# VCO_channel.net
KiCad netlist of a schematic drawn in Altium Designer
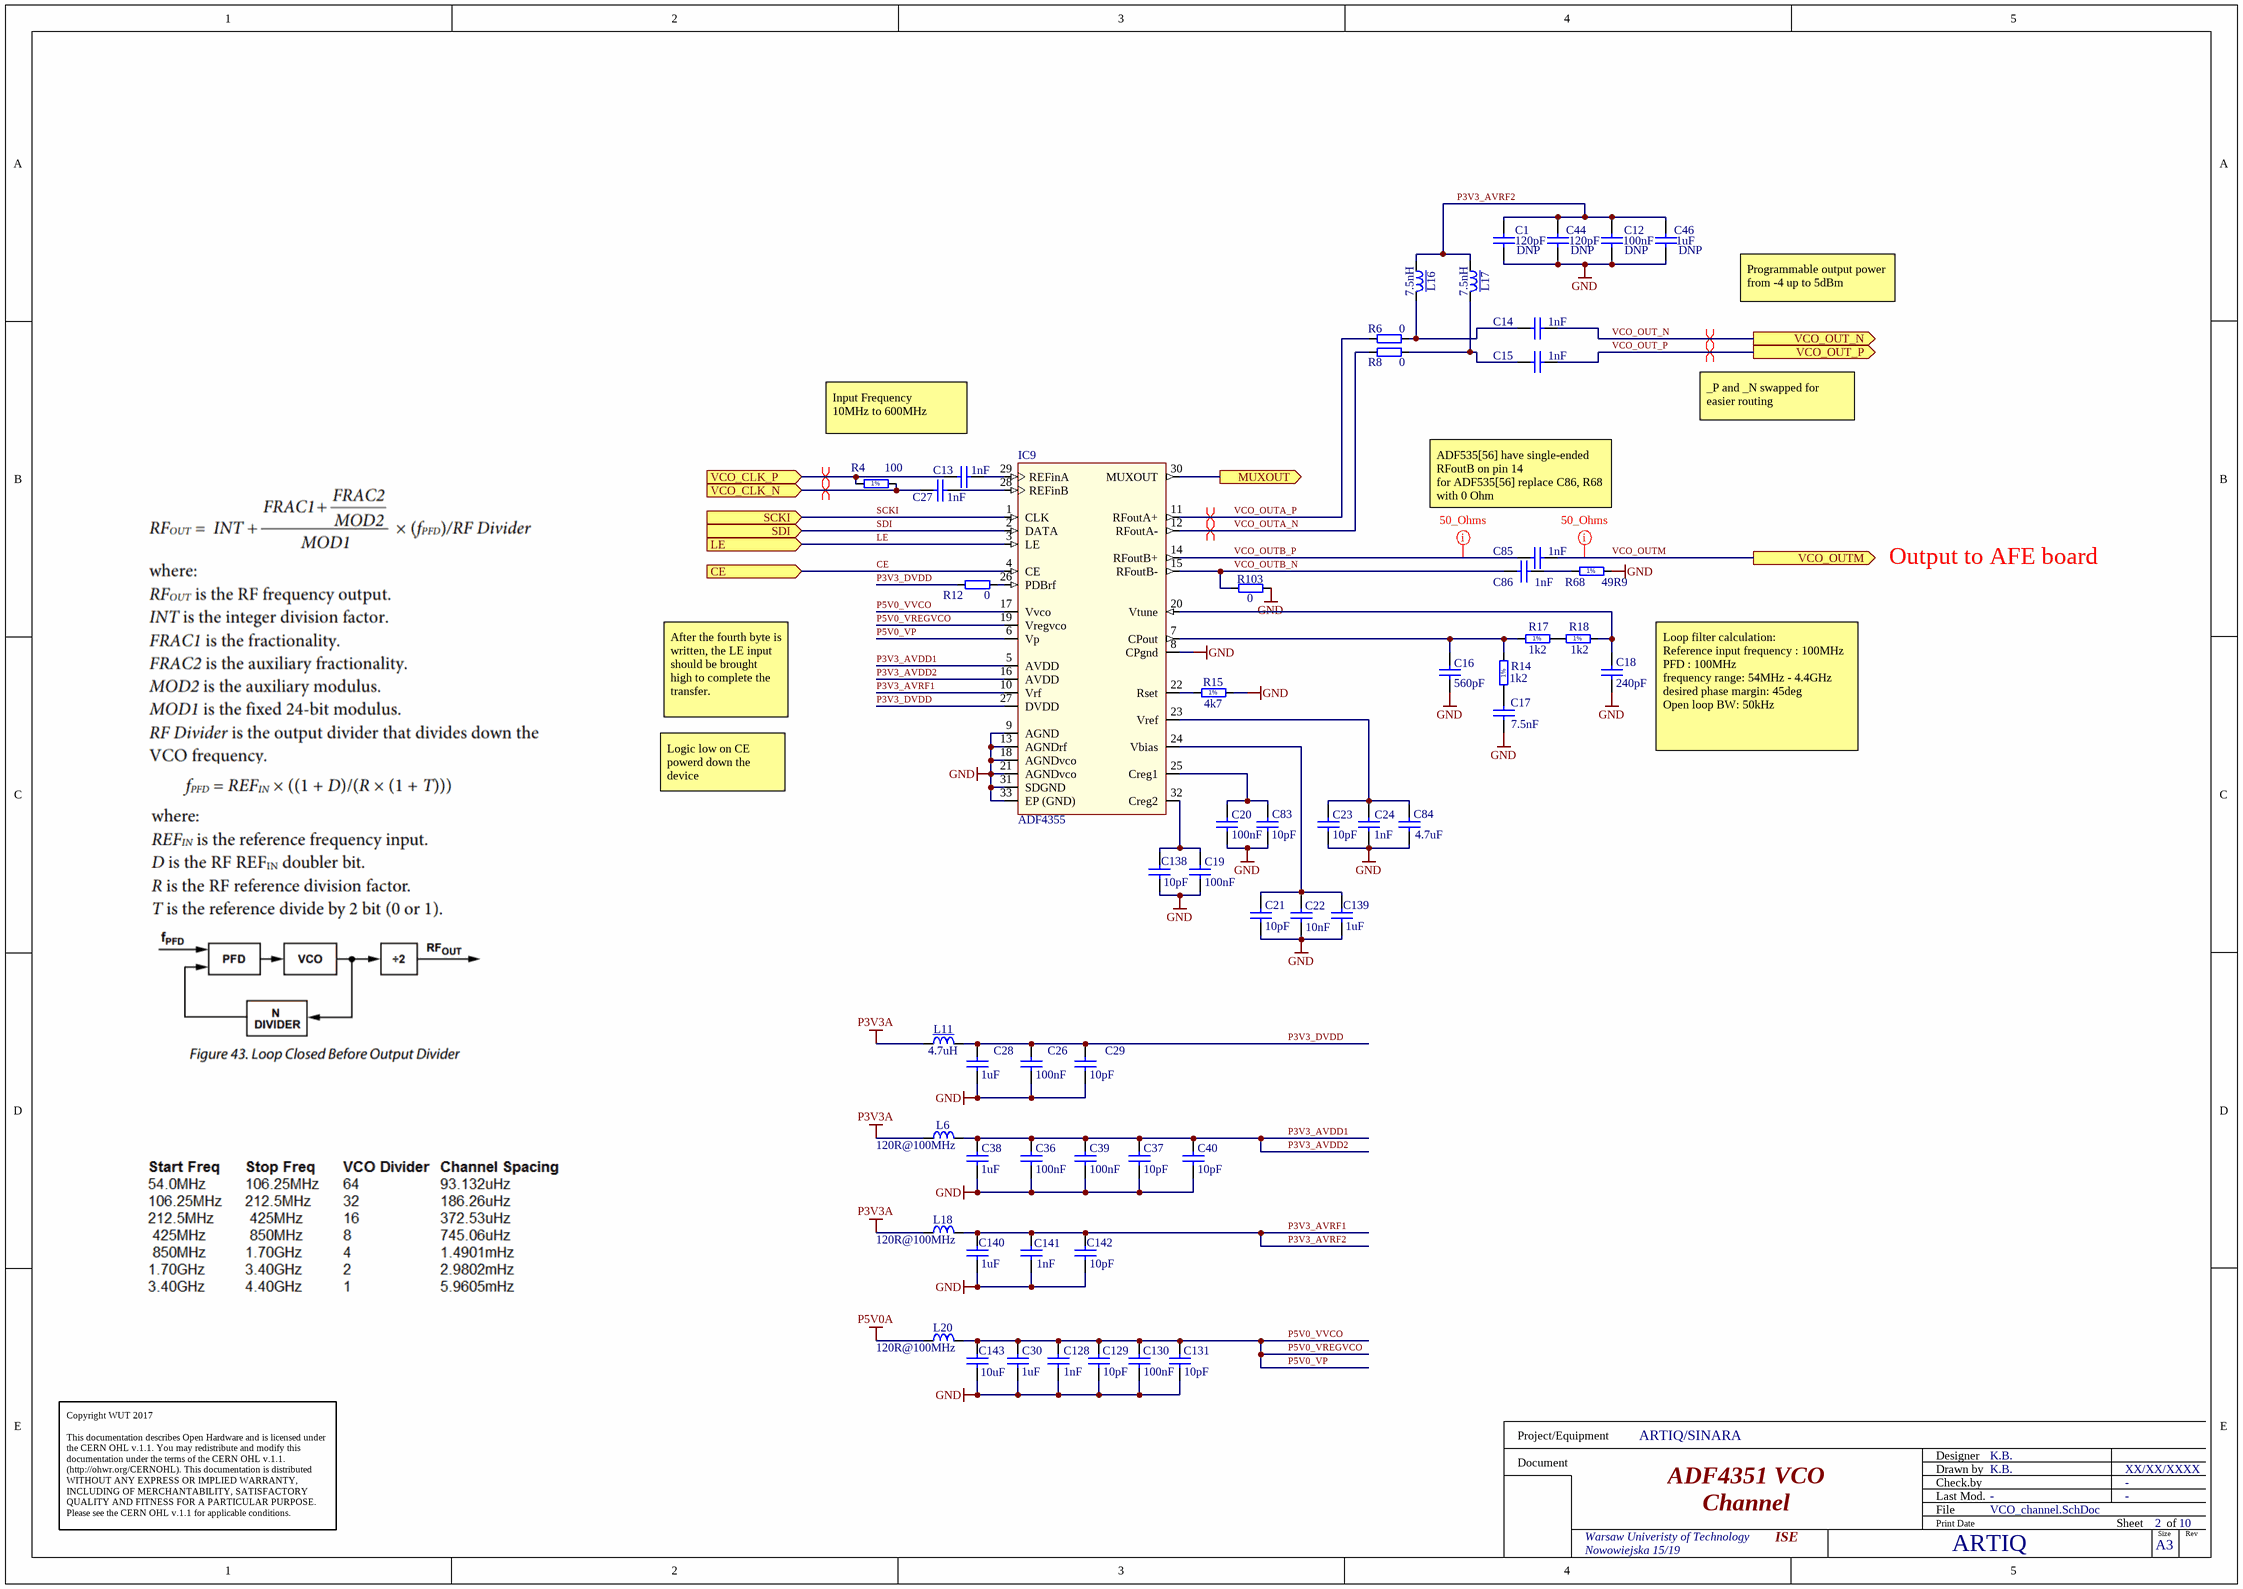
[diagram p0: VCO_channel.SchDoc]

(export (version "E")
  (design (tool "Eeschema 10.0.6"))
  (components
    (comp (ref "C1")
      (value "120pF")
      (footprint "CAPC1005X55N")
      (description "Non-polarised capacitor")
      (fields
        (field (name "PART NUMBER") "CC0402_120PF_50V_5%_C0G")
        (field (name "VOLTAGE") "50V")
        (field (name "MOUNTED") "DNP")
        (field (name "AUTHOR") "CERN DEM JLC")
      )
      (libsource (lib "Capacitors") (part "Capacitor - non polarized"))
    )
    (comp (ref "C12")
      (value "100nF")
      (footprint "CAPC1005X55N")
      (description "Non-polarised capacitor")
      (fields
        (field (name "PART NUMBER") "CC0402_100NF_16V_10%_X5R")
        (field (name "VOLTAGE") "16V")
        (field (name "MOUNTED") "DNP")
        (field (name "AUTHOR") "CERN DEM JLC")
      )
      (libsource (lib "Capacitors") (part "Capacitor - non polarized"))
    )
    (comp (ref "C13")
      (value "1nF")
      (footprint "CAPC1005X55N")
      (description "Non-polarised capacitor")
      (fields
        (field (name "PART NUMBER") "CC0402_1NF_50V_10%_X7R")
        (field (name "VOLTAGE") "50V")
        (field (name "AUTHOR") "CERN DEM JLC")
      )
      (libsource (lib "Capacitors") (part "Capacitor - non polarized"))
    )
    (comp (ref "C14")
      (value "1nF")
      (footprint "CAPC1005X55N")
      (description "Non-polarised capacitor")
      (fields
        (field (name "PART NUMBER") "CC0402_1NF_50V_10%_X7R")
        (field (name "VOLTAGE") "50V")
        (field (name "AUTHOR") "CERN DEM JLC")
      )
      (libsource (lib "Capacitors") (part "Capacitor - non polarized"))
    )
    (comp (ref "C15")
      (value "1nF")
      (footprint "CAPC1005X55N")
      (description "Non-polarised capacitor")
      (fields
        (field (name "PART NUMBER") "CC0402_1NF_50V_10%_X7R")
        (field (name "VOLTAGE") "50V")
        (field (name "AUTHOR") "CERN DEM JLC")
      )
      (libsource (lib "Capacitors") (part "Capacitor - non polarized"))
    )
    (comp (ref "C16")
      (value "560pF")
      (footprint "CAPC1005X55N")
      (description "Non-polarised capacitor")
      (fields
        (field (name "PART NUMBER") "CC0402_560PF_50V_5%_C0G")
        (field (name "VOLTAGE") "50V")
        (field (name "AUTHOR") "CERN DEM JLC")
      )
      (libsource (lib "Capacitors") (part "Capacitor - non polarized"))
    )
    (comp (ref "C17")
      (value "7.5nF")
      (footprint "CAPC1005X55N")
      (description "Non-polarised capacitor")
      (fields
        (field (name "PART NUMBER") "CC0402_7N5F_25V_5%_X7R")
        (field (name "VOLTAGE") "25V")
        (field (name "AUTHOR") "CERN DEM JLC")
      )
      (libsource (lib "Capacitors") (part "Capacitor - non polarized"))
    )
    (comp (ref "C18")
      (value "240pF")
      (footprint "CAPC1005X55N")
      (description "Non-polarised capacitor")
      (fields
        (field (name "PART NUMBER") "CC0402_240PF_50V_5%_C0G")
        (field (name "VOLTAGE") "50V")
        (field (name "AUTHOR") "CERN DEM JLC")
      )
      (libsource (lib "Capacitors") (part "Capacitor - non polarized"))
    )
    (comp (ref "C19")
      (value "100nF")
      (footprint "CAPC1005X55N")
      (description "Non-polarised capacitor")
      (fields
        (field (name "PART NUMBER") "CC0402_100NF_16V_10%_X5R")
        (field (name "VOLTAGE") "16V")
        (field (name "AUTHOR") "CERN DEM JLC")
      )
      (libsource (lib "Capacitors") (part "Capacitor - non polarized"))
    )
    (comp (ref "C20")
      (value "100nF")
      (footprint "CAPC1005X55N")
      (description "Non-polarised capacitor")
      (fields
        (field (name "PART NUMBER") "CC0402_100NF_16V_10%_X5R")
        (field (name "VOLTAGE") "16V")
        (field (name "AUTHOR") "CERN DEM JLC")
      )
      (libsource (lib "Capacitors") (part "Capacitor - non polarized"))
    )
    (comp (ref "C21")
      (value "10pF")
      (footprint "CAPC1005X55N")
      (description "Non-polarised capacitor")
      (fields
        (field (name "PART NUMBER") "CC0402_10PF_50V_5%_C0G")
        (field (name "VOLTAGE") "50V")
        (field (name "AUTHOR") "CERN DEM JLC")
      )
      (libsource (lib "Capacitors") (part "Capacitor - non polarized"))
    )
    (comp (ref "C22")
      (value "10nF")
      (footprint "CAPC1005X55N")
      (description "Non-polarised capacitor")
      (fields
        (field (name "PART NUMBER") "CC0402_10NF_16V_10%_X7R")
        (field (name "VOLTAGE") "16V")
        (field (name "AUTHOR") "CERN DEM JLC")
      )
      (libsource (lib "Capacitors") (part "Capacitor - non polarized"))
    )
    (comp (ref "C23")
      (value "10pF")
      (footprint "CAPC1005X55N")
      (description "Non-polarised capacitor")
      (fields
        (field (name "PART NUMBER") "CC0402_10PF_50V_5%_C0G")
        (field (name "VOLTAGE") "50V")
        (field (name "AUTHOR") "CERN DEM JLC")
      )
      (libsource (lib "Capacitors") (part "Capacitor - non polarized"))
    )
    (comp (ref "C24")
      (value "1nF")
      (footprint "CAPC1005X55N")
      (description "Non-polarised capacitor")
      (fields
        (field (name "PART NUMBER") "CC0402_1NF_50V_10%_X7R")
        (field (name "VOLTAGE") "50V")
        (field (name "AUTHOR") "CERN DEM JLC")
      )
      (libsource (lib "Capacitors") (part "Capacitor - non polarized"))
    )
    (comp (ref "C26")
      (value "100nF")
      (footprint "CAPC1005X55N")
      (description "Non-polarised capacitor")
      (fields
        (field (name "PART NUMBER") "CC0402_100NF_16V_10%_X5R")
        (field (name "VOLTAGE") "16V")
        (field (name "AUTHOR") "CERN DEM JLC")
      )
      (libsource (lib "Capacitors") (part "Capacitor - non polarized"))
    )
    (comp (ref "C27")
      (value "1nF")
      (footprint "CAPC1005X55N")
      (description "Non-polarised capacitor")
      (fields
        (field (name "PART NUMBER") "CC0402_1NF_50V_10%_X7R")
        (field (name "VOLTAGE") "50V")
        (field (name "AUTHOR") "CERN DEM JLC")
      )
      (libsource (lib "Capacitors") (part "Capacitor - non polarized"))
    )
    (comp (ref "C28")
      (value "1uF")
      (footprint "CAPC1005X55N")
      (description "Non-polarised capacitor")
      (fields
        (field (name "PART NUMBER") "CC0402_1UF_16V_10%_X5R")
        (field (name "VOLTAGE") "16V")
        (field (name "AUTHOR") "CERN DEM JLC")
      )
      (libsource (lib "Capacitors") (part "Capacitor - non polarized"))
    )
    (comp (ref "C29")
      (value "10pF")
      (footprint "CAPC1005X55N")
      (description "Non-polarised capacitor")
      (fields
        (field (name "PART NUMBER") "CC0402_10PF_50V_5%_C0G")
        (field (name "VOLTAGE") "50V")
        (field (name "AUTHOR") "CERN DEM JLC")
      )
      (libsource (lib "Capacitors") (part "Capacitor - non polarized"))
    )
    (comp (ref "C30")
      (value "1uF")
      (footprint "CAPC1005X55N")
      (description "Non-polarised capacitor")
      (fields
        (field (name "PART NUMBER") "CC0402_1UF_16V_10%_X5R")
        (field (name "VOLTAGE") "16V")
        (field (name "AUTHOR") "CERN DEM JLC")
      )
      (libsource (lib "Capacitors") (part "Capacitor - non polarized"))
    )
    (comp (ref "C36")
      (value "100nF")
      (footprint "CAPC1005X55N")
      (description "Non-polarised capacitor")
      (fields
        (field (name "PART NUMBER") "CC0402_100NF_16V_10%_X5R")
        (field (name "VOLTAGE") "16V")
        (field (name "AUTHOR") "CERN DEM JLC")
      )
      (libsource (lib "Capacitors") (part "Capacitor - non polarized"))
    )
    (comp (ref "C37")
      (value "10pF")
      (footprint "CAPC1005X55N")
      (description "Non-polarised capacitor")
      (fields
        (field (name "PART NUMBER") "CC0402_10PF_50V_5%_C0G")
        (field (name "VOLTAGE") "50V")
        (field (name "AUTHOR") "CERN DEM JLC")
      )
      (libsource (lib "Capacitors") (part "Capacitor - non polarized"))
    )
    (comp (ref "C38")
      (value "1uF")
      (footprint "CAPC1005X55N")
      (description "Non-polarised capacitor")
      (fields
        (field (name "PART NUMBER") "CC0402_1UF_16V_10%_X5R")
        (field (name "VOLTAGE") "16V")
        (field (name "AUTHOR") "CERN DEM JLC")
      )
      (libsource (lib "Capacitors") (part "Capacitor - non polarized"))
    )
    (comp (ref "C39")
      (value "100nF")
      (footprint "CAPC1005X55N")
      (description "Non-polarised capacitor")
      (fields
        (field (name "PART NUMBER") "CC0402_100NF_16V_10%_X5R")
        (field (name "VOLTAGE") "16V")
        (field (name "AUTHOR") "CERN DEM JLC")
      )
      (libsource (lib "Capacitors") (part "Capacitor - non polarized"))
    )
    (comp (ref "C40")
      (value "10pF")
      (footprint "CAPC1005X55N")
      (description "Non-polarised capacitor")
      (fields
        (field (name "PART NUMBER") "CC0402_10PF_50V_5%_C0G")
        (field (name "VOLTAGE") "50V")
        (field (name "AUTHOR") "CERN DEM JLC")
      )
      (libsource (lib "Capacitors") (part "Capacitor - non polarized"))
    )
    (comp (ref "C44")
      (value "120pF")
      (footprint "CAPC1005X55N")
      (description "Non-polarised capacitor")
      (fields
        (field (name "PART NUMBER") "CC0402_120PF_50V_5%_C0G")
        (field (name "VOLTAGE") "50V")
        (field (name "MOUNTED") "DNP")
        (field (name "AUTHOR") "CERN DEM JLC")
      )
      (libsource (lib "Capacitors") (part "Capacitor - non polarized"))
    )
    (comp (ref "C46")
      (value "1uF")
      (footprint "CAPC1005X55N")
      (description "Non-polarised capacitor")
      (fields
        (field (name "PART NUMBER") "CC0402_1UF_16V_10%_X5R")
        (field (name "VOLTAGE") "16V")
        (field (name "MOUNTED") "DNP")
        (field (name "AUTHOR") "CERN DEM JLC")
      )
      (libsource (lib "Capacitors") (part "Capacitor - non polarized"))
    )
    (comp (ref "C83")
      (value "10pF")
      (footprint "CAPC1005X55N")
      (description "Non-polarised capacitor")
      (fields
        (field (name "PART NUMBER") "CC0402_10PF_50V_5%_C0G")
        (field (name "VOLTAGE") "50V")
        (field (name "AUTHOR") "CERN DEM JLC")
      )
      (libsource (lib "Capacitors") (part "Capacitor - non polarized"))
    )
    (comp (ref "C84")
      (value "4.7uF")
      (footprint "CAPC1608X80N")
      (description "Non-polarised capacitor")
      (fields
        (field (name "PART NUMBER") "CC0603_4U7F_16V_10%_X5R")
        (field (name "VOLTAGE") "16V")
        (field (name "AUTHOR") "CERN DEM MR")
      )
      (libsource (lib "Capacitors") (part "Capacitor - non polarized"))
    )
    (comp (ref "C85")
      (value "1nF")
      (footprint "CAPC1005X55N")
      (description "Non-polarised capacitor")
      (fields
        (field (name "PART NUMBER") "CC0402_1NF_50V_10%_X7R")
        (field (name "VOLTAGE") "50V")
        (field (name "AUTHOR") "CERN DEM JLC")
      )
      (libsource (lib "Capacitors") (part "Capacitor - non polarized"))
    )
    (comp (ref "C86")
      (value "1nF")
      (footprint "CAPC1005X55N")
      (description "Non-polarised capacitor")
      (fields
        (field (name "PART NUMBER") "CC0402_1NF_50V_10%_X7R")
        (field (name "VOLTAGE") "50V")
        (field (name "AUTHOR") "CERN DEM JLC")
      )
      (libsource (lib "Capacitors") (part "Capacitor - non polarized"))
    )
    (comp (ref "C128")
      (value "1nF")
      (footprint "CAPC1005X55N")
      (description "Non-polarised capacitor")
      (fields
        (field (name "PART NUMBER") "CC0402_1NF_50V_10%_X7R")
        (field (name "VOLTAGE") "50V")
        (field (name "AUTHOR") "CERN DEM JLC")
      )
      (libsource (lib "Capacitors") (part "Capacitor - non polarized"))
    )
    (comp (ref "C129")
      (value "10pF")
      (footprint "CAPC1005X55N")
      (description "Non-polarised capacitor")
      (fields
        (field (name "PART NUMBER") "CC0402_10PF_50V_5%_C0G")
        (field (name "VOLTAGE") "50V")
        (field (name "AUTHOR") "CERN DEM JLC")
      )
      (libsource (lib "Capacitors") (part "Capacitor - non polarized"))
    )
    (comp (ref "C130")
      (value "100nF")
      (footprint "CAPC1005X55N")
      (description "Non-polarised capacitor")
      (fields
        (field (name "PART NUMBER") "CC0402_100NF_16V_10%_X5R")
        (field (name "VOLTAGE") "16V")
        (field (name "AUTHOR") "CERN DEM JLC")
      )
      (libsource (lib "Capacitors") (part "Capacitor - non polarized"))
    )
    (comp (ref "C131")
      (value "10pF")
      (footprint "CAPC1005X55N")
      (description "Non-polarised capacitor")
      (fields
        (field (name "PART NUMBER") "CC0402_10PF_50V_5%_C0G")
        (field (name "VOLTAGE") "50V")
        (field (name "AUTHOR") "CERN DEM JLC")
      )
      (libsource (lib "Capacitors") (part "Capacitor - non polarized"))
    )
    (comp (ref "C138")
      (value "10pF")
      (footprint "CAPC1005X55N")
      (description "Non-polarised capacitor")
      (fields
        (field (name "PART NUMBER") "CC0402_10PF_50V_5%_C0G")
        (field (name "VOLTAGE") "50V")
        (field (name "AUTHOR") "CERN DEM JLC")
      )
      (libsource (lib "Capacitors") (part "Capacitor - non polarized"))
    )
    (comp (ref "C139")
      (value "1uF")
      (footprint "CAPC1005X55N")
      (description "Non-polarised capacitor")
      (fields
        (field (name "PART NUMBER") "CC0402_1UF_16V_10%_X5R")
        (field (name "VOLTAGE") "16V")
        (field (name "AUTHOR") "CERN DEM JLC")
      )
      (libsource (lib "Capacitors") (part "Capacitor - non polarized"))
    )
    (comp (ref "C140")
      (value "1uF")
      (footprint "CAPC1005X55N")
      (description "Non-polarised capacitor")
      (fields
        (field (name "PART NUMBER") "CC0402_1UF_16V_10%_X5R")
        (field (name "VOLTAGE") "16V")
        (field (name "AUTHOR") "CERN DEM JLC")
      )
      (libsource (lib "Capacitors") (part "Capacitor - non polarized"))
    )
    (comp (ref "C141")
      (value "1nF")
      (footprint "CAPC1005X55N")
      (description "Non-polarised capacitor")
      (fields
        (field (name "PART NUMBER") "CC0402_1NF_50V_10%_X7R")
        (field (name "VOLTAGE") "50V")
        (field (name "AUTHOR") "CERN DEM JLC")
      )
      (libsource (lib "Capacitors") (part "Capacitor - non polarized"))
    )
    (comp (ref "C142")
      (value "10pF")
      (footprint "CAPC1005X55N")
      (description "Non-polarised capacitor")
      (fields
        (field (name "PART NUMBER") "CC0402_10PF_50V_5%_C0G")
        (field (name "VOLTAGE") "50V")
        (field (name "AUTHOR") "CERN DEM JLC")
      )
      (libsource (lib "Capacitors") (part "Capacitor - non polarized"))
    )
    (comp (ref "C143")
      (value "10uF")
      (footprint "CAPC1608X80N")
      (description "Non-polarised capacitor")
      (fields
        (field (name "PART NUMBER") "CC0603_10UF_16V_20%_X5R")
        (field (name "VOLTAGE") "16V")
        (field (name "AUTHOR") "CERN DEM MR")
      )
      (libsource (lib "Capacitors") (part "Capacitor - non polarized"))
    )
    (comp (ref "IC9")
      (value "ADF4355")
      (footprint "CP-32-7_N")
      (description "54MHz to 4400MHz Frequency Synthesizer")
      (fields
        (field (name "MANUFACTURER") "Analog Devices")
        (field (name "MANUFACTURER PART NUMBER") "ADF4355-2BCPZ")
      )
      (libsource (lib "AD RF and IF Frequency Synthesiser") (part "ADF4355"))
    )
    (comp (ref "L6")
      (value "120R@100MHz")
      (footprint "INDC1608X95N")
      (description "Inductor")
      (fields
        (field (name "PART NUMBER") "IND0603_MURATA_BLM18PG121SN1D")
        (field (name "POWER") "2A")
        (field (name "AUTHOR") "CERN DEM BC")
      )
      (libsource (lib "Inductors & Transformers") (part "Inductor"))
    )
    (comp (ref "L11")
      (value "4.7uH")
      (footprint "INDC2012X145N")
      (description "Inductor With Core")
      (fields
        (field (name "PART NUMBER") "IND0805_4.7UH_20%_KEMET_L-DWI")
        (field (name "POWER") "360mA")
        (field (name "AUTHOR") "CERN DEM JLC")
      )
      (libsource (lib "Inductors & Transformers") (part "Inductor With Magnetic core"))
    )
    (comp (ref "L16")
      (value "7.5nH")
      (footprint "IND_COILCRAFT_0402DC")
      (description "Inductor With Core")
      (fields
        (field (name "PART NUMBER") "IND0402_7.5NH_2%_COILCRAFT_0402DC")
        (field (name "POWER") "1.65A")
        (field (name "AUTHOR") "GK")
      )
      (libsource (lib "Inductors_Transformers") (part "IND0402_7.5NH_2%_COILCRAFT_0402DC"))
    )
    (comp (ref "L17")
      (value "7.5nH")
      (footprint "IND_COILCRAFT_0402DC")
      (description "Inductor With Core")
      (fields
        (field (name "PART NUMBER") "IND0402_7.5NH_2%_COILCRAFT_0402DC")
        (field (name "POWER") "1.65A")
        (field (name "AUTHOR") "GK")
      )
      (libsource (lib "Inductors_Transformers") (part "IND0402_7.5NH_2%_COILCRAFT_0402DC"))
    )
    (comp (ref "L18")
      (value "120R@100MHz")
      (footprint "INDC1608X95N")
      (description "Inductor")
      (fields
        (field (name "PART NUMBER") "IND0603_MURATA_BLM18PG121SN1D")
        (field (name "POWER") "2A")
        (field (name "AUTHOR") "CERN DEM BC")
      )
      (libsource (lib "Inductors & Transformers") (part "Inductor"))
    )
    (comp (ref "L20")
      (value "120R@100MHz")
      (footprint "INDC1608X95N")
      (description "Inductor")
      (fields
        (field (name "PART NUMBER") "IND0603_MURATA_BLM18PG121SN1D")
        (field (name "POWER") "2A")
        (field (name "AUTHOR") "CERN DEM BC")
      )
      (libsource (lib "Inductors & Transformers") (part "Inductor"))
    )
    (comp (ref "R4")
      (value "100")
      (footprint "RESC1005X40N")
      (description "Resistor - 1%")
      (fields
        (field (name "PART NUMBER") "R0402_100R_1%_0.0625W_100PPM")
        (field (name "POWER") "0.0625W")
        (field (name "AUTHOR") "CERN DEM JLC")
      )
      (libsource (lib "Resistors") (part "Resistor - 1%"))
    )
    (comp (ref "R6")
      (value "0")
      (footprint "RESC1005X40N")
      (description "Resistor")
      (fields
        (field (name "PART NUMBER") "R0402_0R_JUMPER")
        (field (name "MANUFACTURER") "GENERIC")
        (field (name "AUTHOR") "CERN DEM JLC")
      )
      (libsource (lib "Resistors") (part "Resistor"))
    )
    (comp (ref "R8")
      (value "0")
      (footprint "RESC1005X40N")
      (description "Resistor")
      (fields
        (field (name "PART NUMBER") "R0402_0R_JUMPER")
        (field (name "MANUFACTURER") "GENERIC")
        (field (name "AUTHOR") "CERN DEM JLC")
      )
      (libsource (lib "Resistors") (part "Resistor"))
    )
    (comp (ref "R12")
      (value "0")
      (footprint "RESC1005X40N")
      (description "Resistor")
      (fields
        (field (name "PART NUMBER") "R0402_0R_JUMPER")
        (field (name "MANUFACTURER") "GENERIC")
        (field (name "AUTHOR") "CERN DEM JLC")
      )
      (libsource (lib "Resistors") (part "Resistor"))
    )
    (comp (ref "R14")
      (value "1k2")
      (footprint "RESC1005X40N")
      (description "Resistor - 1%")
      (fields
        (field (name "PART NUMBER") "R0402_1K2_1%_0.0625W_100PPM")
        (field (name "POWER") "0.0625W")
        (field (name "AUTHOR") "CERN DEM JLC")
      )
      (libsource (lib "Resistors") (part "Resistor - 1%"))
    )
    (comp (ref "R15")
      (value "4k7")
      (footprint "RESC1005X40N")
      (description "Resistor - 1%")
      (fields
        (field (name "PART NUMBER") "R0402_4K7_1%_0.0625W_100PPM")
        (field (name "POWER") "0.0625W")
        (field (name "AUTHOR") "CERN DEM JLC")
      )
      (libsource (lib "Resistors") (part "Resistor - 1%"))
    )
    (comp (ref "R17")
      (value "1k2")
      (footprint "RESC1005X40N")
      (description "Resistor - 1%")
      (fields
        (field (name "PART NUMBER") "R0402_1K2_1%_0.0625W_100PPM")
        (field (name "POWER") "0.0625W")
        (field (name "AUTHOR") "CERN DEM JLC")
      )
      (libsource (lib "Resistors") (part "Resistor - 1%"))
    )
    (comp (ref "R18")
      (value "1k2")
      (footprint "RESC1005X40N")
      (description "Resistor - 1%")
      (fields
        (field (name "PART NUMBER") "R0402_1K2_1%_0.0625W_100PPM")
        (field (name "POWER") "0.0625W")
        (field (name "AUTHOR") "CERN DEM JLC")
      )
      (libsource (lib "Resistors") (part "Resistor - 1%"))
    )
    (comp (ref "R68")
      (value "49R9")
      (footprint "RESC1005X40N")
      (description "Resistor - 1%")
      (fields
        (field (name "PART NUMBER") "R0402_49R9_1%_0.0625W_100PPM")
        (field (name "POWER") "0.0625W")
        (field (name "AUTHOR") "CERN DEM JLC")
      )
      (libsource (lib "Resistors") (part "Resistor - 1%"))
    )
    (comp (ref "R103")
      (value "0")
      (footprint "RESC1005X40N")
      (description "Resistor")
      (fields
        (field (name "PART NUMBER") "R0402_0R_JUMPER")
        (field (name "MANUFACTURER") "GENERIC")
        (field (name "AUTHOR") "CERN DEM JLC")
      )
      (libsource (lib "Resistors") (part "Resistor"))
    )
  )
  (nets
    (net (code "1") (name "/CE") (class "Default")
      (node (ref "IC9") (pin "4") (pinfunction "CE_4") (pintype "input"))
    )
    (net (code "2") (name "/LE") (class "Default")
      (node (ref "IC9") (pin "3") (pinfunction "LE_3") (pintype "input"))
    )
    (net (code "3") (name "/MUXOUT") (class "Default")
      (node (ref "IC9") (pin "30") (pinfunction "MUXOUT_30") (pintype "output"))
    )
    (net (code "4") (name "/P3V3_AVDD1") (class "Default")
      (node (ref "C36") (pin "2") (pinfunction "2_2") (pintype "passive"))
      (node (ref "C37") (pin "2") (pinfunction "2_2") (pintype "passive"))
      (node (ref "C38") (pin "2") (pinfunction "2_2") (pintype "passive"))
      (node (ref "C39") (pin "2") (pinfunction "2_2") (pintype "passive"))
      (node (ref "C40") (pin "2") (pinfunction "2_2") (pintype "passive"))
      (node (ref "IC9") (pin "16") (pinfunction "AVDD_16") (pintype "power_in"))
      (node (ref "IC9") (pin "5") (pinfunction "AVDD_5") (pintype "power_in"))
      (node (ref "L6") (pin "1") (pinfunction "1_1") (pintype "passive"))
    )
    (net (code "5") (name "/P3V3_AVRF1") (class "Default")
      (node (ref "C1") (pin "2") (pinfunction "2_2") (pintype "passive"))
      (node (ref "C12") (pin "2") (pinfunction "2_2") (pintype "passive"))
      (node (ref "C140") (pin "2") (pinfunction "2_2") (pintype "passive"))
      (node (ref "C141") (pin "2") (pinfunction "2_2") (pintype "passive"))
      (node (ref "C142") (pin "2") (pinfunction "2_2") (pintype "passive"))
      (node (ref "C44") (pin "2") (pinfunction "2_2") (pintype "passive"))
      (node (ref "C46") (pin "2") (pinfunction "2_2") (pintype "passive"))
      (node (ref "IC9") (pin "10") (pinfunction "Vrf_10") (pintype "power_in"))
      (node (ref "L16") (pin "1") (pinfunction "1_1") (pintype "passive"))
      (node (ref "L17") (pin "1") (pinfunction "1_1") (pintype "passive"))
      (node (ref "L18") (pin "1") (pinfunction "1_1") (pintype "passive"))
    )
    (net (code "6") (name "/P3V3_DVDD") (class "Default")
      (node (ref "C26") (pin "2") (pinfunction "2_2") (pintype "passive"))
      (node (ref "C28") (pin "2") (pinfunction "2_2") (pintype "passive"))
      (node (ref "C29") (pin "2") (pinfunction "2_2") (pintype "passive"))
      (node (ref "IC9") (pin "27") (pinfunction "DVDD_27") (pintype "power_in"))
      (node (ref "L11") (pin "2") (pinfunction "2_2") (pintype "passive"))
      (node (ref "R12") (pin "1") (pinfunction "1_1") (pintype "passive"))
    )
    (net (code "7") (name "/P5V0_VP") (class "Default")
      (node (ref "C128") (pin "2") (pinfunction "2_2") (pintype "passive"))
      (node (ref "C129") (pin "2") (pinfunction "2_2") (pintype "passive"))
      (node (ref "C130") (pin "2") (pinfunction "2_2") (pintype "passive"))
      (node (ref "C131") (pin "2") (pinfunction "2_2") (pintype "passive"))
      (node (ref "C143") (pin "2") (pinfunction "2_2") (pintype "passive"))
      (node (ref "C30") (pin "2") (pinfunction "2_2") (pintype "passive"))
      (node (ref "IC9") (pin "17") (pinfunction "Vvco_17") (pintype "power_in"))
      (node (ref "IC9") (pin "19") (pinfunction "Vregvco_19") (pintype "power_in"))
      (node (ref "IC9") (pin "6") (pinfunction "Vp_6") (pintype "power_in"))
      (node (ref "L20") (pin "1") (pinfunction "1_1") (pintype "passive"))
    )
    (net (code "8") (name "/SCKI") (class "Default")
      (node (ref "IC9") (pin "1") (pinfunction "CLK_1") (pintype "input"))
    )
    (net (code "9") (name "/SDI") (class "Default")
      (node (ref "IC9") (pin "2") (pinfunction "DATA_2") (pintype "input"))
    )
    (net (code "10") (name "/VCO_CLK_N") (class "Default")
      (node (ref "C27") (pin "1") (pinfunction "1_1") (pintype "passive"))
      (node (ref "R4") (pin "2") (pinfunction "2_2") (pintype "passive"))
    )
    (net (code "11") (name "/VCO_CLK_P") (class "Default")
      (node (ref "C13") (pin "1") (pinfunction "1_1") (pintype "passive"))
      (node (ref "R4") (pin "1") (pinfunction "1_1") (pintype "passive"))
    )
    (net (code "12") (name "/VCO_OUTA_N") (class "Default")
      (node (ref "IC9") (pin "12") (pinfunction "RFoutA-_12") (pintype "output"))
      (node (ref "R8") (pin "1") (pinfunction "1_1") (pintype "passive"))
    )
    (net (code "13") (name "/VCO_OUTA_P") (class "Default")
      (node (ref "IC9") (pin "11") (pinfunction "RFoutA+_11") (pintype "output"))
      (node (ref "R6") (pin "1") (pinfunction "1_1") (pintype "passive"))
    )
    (net (code "14") (name "/VCO_OUTB_N") (class "Default")
      (node (ref "C86") (pin "1") (pinfunction "1_1") (pintype "passive"))
      (node (ref "IC9") (pin "15") (pinfunction "RFoutB-_15") (pintype "output"))
      (node (ref "R103") (pin "1") (pinfunction "1_1") (pintype "passive"))
    )
    (net (code "15") (name "/VCO_OUTB_P") (class "Default")
      (node (ref "C85") (pin "1") (pinfunction "1_1") (pintype "passive"))
      (node (ref "IC9") (pin "14") (pinfunction "RFoutB+_14") (pintype "output"))
    )
    (net (code "16") (name "/VCO_OUTM") (class "Default")
      (node (ref "C85") (pin "2") (pinfunction "2_2") (pintype "passive"))
    )
    (net (code "17") (name "/VCO_OUT_N") (class "Default")
      (node (ref "C14") (pin "2") (pinfunction "2_2") (pintype "passive"))
    )
    (net (code "18") (name "/VCO_OUT_P") (class "Default")
      (node (ref "C15") (pin "2") (pinfunction "2_2") (pintype "passive"))
    )
    (net (code "19") (name "GND") (class "Default")
      (node (ref "C1") (pin "1") (pinfunction "1_1") (pintype "passive"))
      (node (ref "C12") (pin "1") (pinfunction "1_1") (pintype "passive"))
      (node (ref "C128") (pin "1") (pinfunction "1_1") (pintype "passive"))
      (node (ref "C129") (pin "1") (pinfunction "1_1") (pintype "passive"))
      (node (ref "C130") (pin "1") (pinfunction "1_1") (pintype "passive"))
      (node (ref "C131") (pin "1") (pinfunction "1_1") (pintype "passive"))
      (node (ref "C138") (pin "1") (pinfunction "1_1") (pintype "passive"))
      (node (ref "C139") (pin "1") (pinfunction "1_1") (pintype "passive"))
      (node (ref "C140") (pin "1") (pinfunction "1_1") (pintype "passive"))
      (node (ref "C141") (pin "1") (pinfunction "1_1") (pintype "passive"))
      (node (ref "C142") (pin "1") (pinfunction "1_1") (pintype "passive"))
      (node (ref "C143") (pin "1") (pinfunction "1_1") (pintype "passive"))
      (node (ref "C16") (pin "1") (pinfunction "1_1") (pintype "passive"))
      (node (ref "C17") (pin "1") (pinfunction "1_1") (pintype "passive"))
      (node (ref "C18") (pin "1") (pinfunction "1_1") (pintype "passive"))
      (node (ref "C19") (pin "1") (pinfunction "1_1") (pintype "passive"))
      (node (ref "C20") (pin "1") (pinfunction "1_1") (pintype "passive"))
      (node (ref "C21") (pin "1") (pinfunction "1_1") (pintype "passive"))
      (node (ref "C22") (pin "1") (pinfunction "1_1") (pintype "passive"))
      (node (ref "C23") (pin "1") (pinfunction "1_1") (pintype "passive"))
      (node (ref "C24") (pin "1") (pinfunction "1_1") (pintype "passive"))
      (node (ref "C26") (pin "1") (pinfunction "1_1") (pintype "passive"))
      (node (ref "C28") (pin "1") (pinfunction "1_1") (pintype "passive"))
      (node (ref "C29") (pin "1") (pinfunction "1_1") (pintype "passive"))
      (node (ref "C30") (pin "1") (pinfunction "1_1") (pintype "passive"))
      (node (ref "C36") (pin "1") (pinfunction "1_1") (pintype "passive"))
      (node (ref "C37") (pin "1") (pinfunction "1_1") (pintype "passive"))
      (node (ref "C38") (pin "1") (pinfunction "1_1") (pintype "passive"))
      (node (ref "C39") (pin "1") (pinfunction "1_1") (pintype "passive"))
      (node (ref "C40") (pin "1") (pinfunction "1_1") (pintype "passive"))
      (node (ref "C44") (pin "1") (pinfunction "1_1") (pintype "passive"))
      (node (ref "C46") (pin "1") (pinfunction "1_1") (pintype "passive"))
      (node (ref "C83") (pin "1") (pinfunction "1_1") (pintype "passive"))
      (node (ref "C84") (pin "1") (pinfunction "1_1") (pintype "passive"))
      (node (ref "IC9") (pin "13") (pinfunction "AGNDrf_13") (pintype "passive"))
      (node (ref "IC9") (pin "18") (pinfunction "AGNDvco_18") (pintype "passive"))
      (node (ref "IC9") (pin "21") (pinfunction "AGNDvco_21") (pintype "passive"))
      (node (ref "IC9") (pin "31") (pinfunction "SDGND_31") (pintype "power_in"))
      (node (ref "IC9") (pin "33") (pinfunction "EP_(GND)_33") (pintype "power_in"))
      (node (ref "IC9") (pin "8") (pinfunction "CPgnd_8") (pintype "power_in"))
      (node (ref "IC9") (pin "9") (pinfunction "AGND_9") (pintype "power_in"))
      (node (ref "R103") (pin "2") (pinfunction "2_2") (pintype "passive"))
      (node (ref "R15") (pin "2") (pinfunction "2_2") (pintype "passive"))
      (node (ref "R68") (pin "2") (pinfunction "2_2") (pintype "passive"))
    )
    (net (code "20") (name "Net-(C14-Pad1)") (class "Default")
      (node (ref "C14") (pin "1") (pinfunction "1_1") (pintype "passive"))
      (node (ref "L16") (pin "2") (pinfunction "2_2") (pintype "passive"))
      (node (ref "R6") (pin "2") (pinfunction "2_2") (pintype "passive"))
    )
    (net (code "21") (name "Net-(C15-Pad1)") (class "Default")
      (node (ref "C15") (pin "1") (pinfunction "1_1") (pintype "passive"))
      (node (ref "L17") (pin "2") (pinfunction "2_2") (pintype "passive"))
      (node (ref "R8") (pin "2") (pinfunction "2_2") (pintype "passive"))
    )
    (net (code "22") (name "Net-(C17-Pad2)") (class "Default")
      (node (ref "C17") (pin "2") (pinfunction "2_2") (pintype "passive"))
      (node (ref "R14") (pin "1") (pinfunction "1_1") (pintype "passive"))
    )
    (net (code "23") (name "Net-(C86-Pad2)") (class "Default")
      (node (ref "C86") (pin "2") (pinfunction "2_2") (pintype "passive"))
      (node (ref "R68") (pin "1") (pinfunction "1_1") (pintype "passive"))
    )
    (net (code "24") (name "Net-(IC9-CPout)") (class "Default")
      (node (ref "C16") (pin "2") (pinfunction "2_2") (pintype "passive"))
      (node (ref "IC9") (pin "7") (pinfunction "CPout_7") (pintype "output"))
      (node (ref "R14") (pin "2") (pinfunction "2_2") (pintype "passive"))
      (node (ref "R17") (pin "1") (pinfunction "1_1") (pintype "passive"))
    )
    (net (code "25") (name "Net-(IC9-Creg1)") (class "Default")
      (node (ref "C20") (pin "2") (pinfunction "2_2") (pintype "passive"))
      (node (ref "C83") (pin "2") (pinfunction "2_2") (pintype "passive"))
      (node (ref "IC9") (pin "25") (pinfunction "Creg1_25") (pintype "passive"))
    )
    (net (code "26") (name "Net-(IC9-Creg2)") (class "Default")
      (node (ref "C138") (pin "2") (pinfunction "2_2") (pintype "passive"))
      (node (ref "C19") (pin "2") (pinfunction "2_2") (pintype "passive"))
      (node (ref "IC9") (pin "32") (pinfunction "Creg2_32") (pintype "passive"))
    )
    (net (code "27") (name "Net-(IC9-PDBrf)") (class "Default")
      (node (ref "IC9") (pin "26") (pinfunction "PDBrf_26") (pintype "input"))
      (node (ref "R12") (pin "2") (pinfunction "2_2") (pintype "passive"))
    )
    (net (code "28") (name "Net-(IC9-REFinA)") (class "Default")
      (node (ref "C13") (pin "2") (pinfunction "2_2") (pintype "passive"))
      (node (ref "IC9") (pin "29") (pinfunction "REFinA_29") (pintype "input"))
    )
    (net (code "29") (name "Net-(IC9-REFinB)") (class "Default")
      (node (ref "C27") (pin "2") (pinfunction "2_2") (pintype "passive"))
      (node (ref "IC9") (pin "28") (pinfunction "REFinB_28") (pintype "input"))
    )
    (net (code "30") (name "Net-(IC9-Rset)") (class "Default")
      (node (ref "IC9") (pin "22") (pinfunction "Rset_22") (pintype "passive"))
      (node (ref "R15") (pin "1") (pinfunction "1_1") (pintype "passive"))
    )
    (net (code "31") (name "Net-(IC9-Vbias)") (class "Default")
      (node (ref "C139") (pin "2") (pinfunction "2_2") (pintype "passive"))
      (node (ref "C21") (pin "2") (pinfunction "2_2") (pintype "passive"))
      (node (ref "C22") (pin "2") (pinfunction "2_2") (pintype "passive"))
      (node (ref "IC9") (pin "24") (pinfunction "Vbias_24") (pintype "passive"))
    )
    (net (code "32") (name "Net-(IC9-Vref)") (class "Default")
      (node (ref "C23") (pin "2") (pinfunction "2_2") (pintype "passive"))
      (node (ref "C24") (pin "2") (pinfunction "2_2") (pintype "passive"))
      (node (ref "C84") (pin "2") (pinfunction "2_2") (pintype "passive"))
      (node (ref "IC9") (pin "23") (pinfunction "Vref_23") (pintype "passive"))
    )
    (net (code "33") (name "Net-(IC9-Vtune)") (class "Default")
      (node (ref "C18") (pin "2") (pinfunction "2_2") (pintype "passive"))
      (node (ref "IC9") (pin "20") (pinfunction "Vtune_20") (pintype "input"))
      (node (ref "R18") (pin "2") (pinfunction "2_2") (pintype "passive"))
    )
    (net (code "34") (name "Net-(R17-Pad2)") (class "Default")
      (node (ref "R17") (pin "2") (pinfunction "2_2") (pintype "passive"))
      (node (ref "R18") (pin "1") (pinfunction "1_1") (pintype "passive"))
    )
    (net (code "35") (name "P3V3A") (class "Default")
      (node (ref "L11") (pin "1") (pinfunction "1_1") (pintype "passive"))
      (node (ref "L18") (pin "2") (pinfunction "2_2") (pintype "passive"))
      (node (ref "L6") (pin "2") (pinfunction "2_2") (pintype "passive"))
    )
    (net (code "36") (name "P5V0A") (class "Default")
      (node (ref "L20") (pin "2") (pinfunction "2_2") (pintype "passive"))
    )
  )
)
